# usb-100basefx.net
KiCad netlist of a schematic drawn in EAGLE
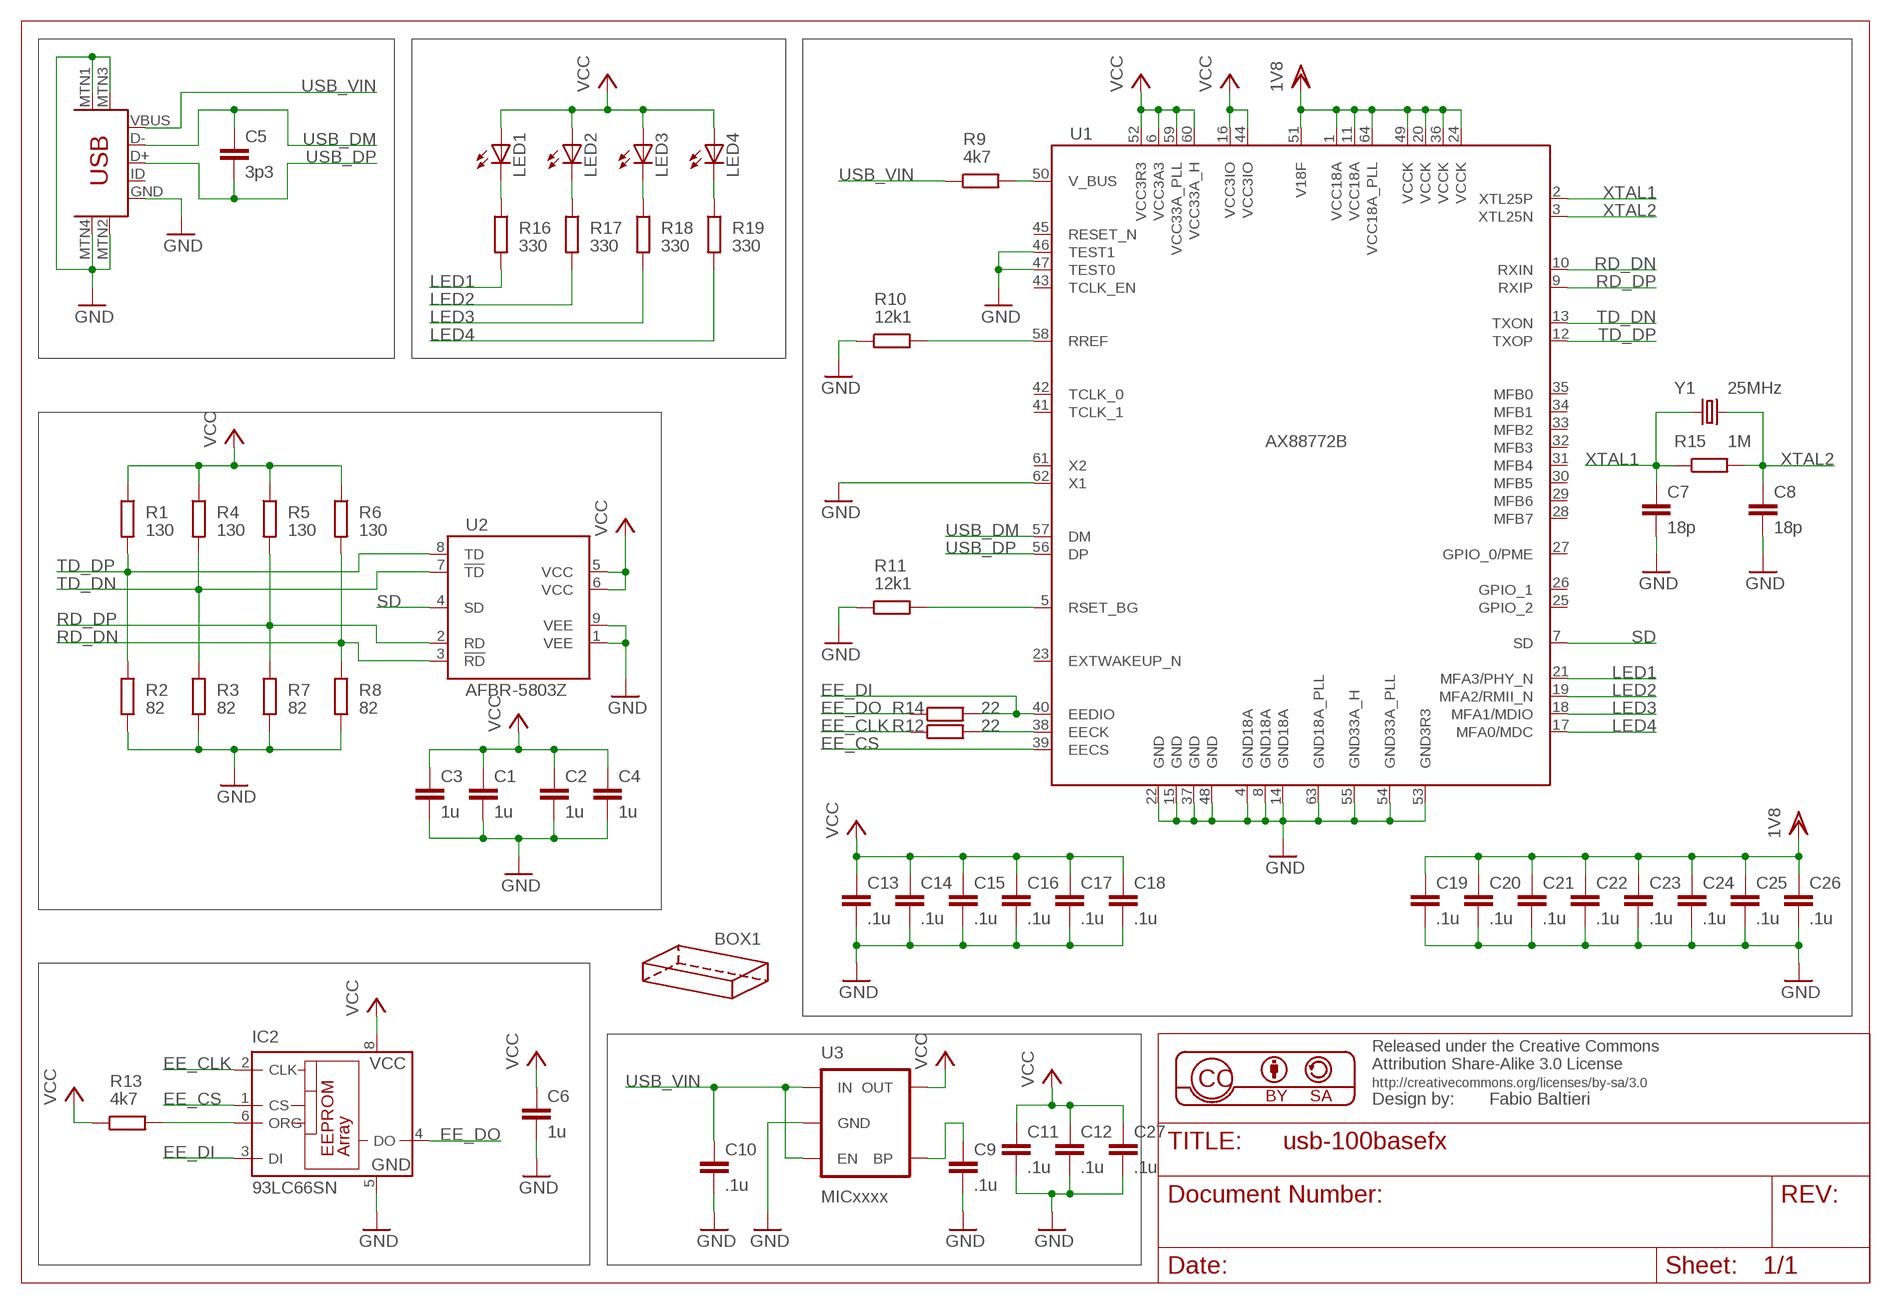
[diagram p0: schematic, sheet 1]

(export (version "E")
  (design (tool "Eeschema 10.0.6"))
  (components
    (comp (ref "BOX1")
      (value "HAMMOND-BOX-R")
      (footprint "eagle-import:1551R")
      (libsource (lib "eagle-import") (part "HAMMOND-BOX-R"))
    )
    (comp (ref "C1")
      (value "1u")
      (footprint "eagle-import:C0603")
      (libsource (lib "eagle-import") (part "C-EUC0603"))
    )
    (comp (ref "C2")
      (value "1u")
      (footprint "eagle-import:C0603")
      (libsource (lib "eagle-import") (part "C-EUC0603"))
    )
    (comp (ref "C3")
      (value "1u")
      (footprint "eagle-import:C0603")
      (libsource (lib "eagle-import") (part "C-EUC0603"))
    )
    (comp (ref "C4")
      (value "1u")
      (footprint "eagle-import:C0603")
      (libsource (lib "eagle-import") (part "C-EUC0603"))
    )
    (comp (ref "C5")
      (value "3p3")
      (footprint "eagle-import:C0603")
      (libsource (lib "eagle-import") (part "C-EUC0603"))
    )
    (comp (ref "C6")
      (value "1u")
      (footprint "eagle-import:C0603")
      (libsource (lib "eagle-import") (part "C-EUC0603"))
    )
    (comp (ref "C7")
      (value "18p")
      (footprint "eagle-import:C0603")
      (libsource (lib "eagle-import") (part "C-EUC0603"))
    )
    (comp (ref "C8")
      (value "18p")
      (footprint "eagle-import:C0603")
      (libsource (lib "eagle-import") (part "C-EUC0603"))
    )
    (comp (ref "C9")
      (value ".1u")
      (footprint "eagle-import:C0603")
      (libsource (lib "eagle-import") (part "C-EUC0603"))
    )
    (comp (ref "C10")
      (value ".1u")
      (footprint "eagle-import:C0603")
      (libsource (lib "eagle-import") (part "C-EUC0603"))
    )
    (comp (ref "C11")
      (value ".1u")
      (footprint "eagle-import:C0603")
      (libsource (lib "eagle-import") (part "C-EUC0603"))
    )
    (comp (ref "C12")
      (value ".1u")
      (footprint "eagle-import:C0603")
      (libsource (lib "eagle-import") (part "C-EUC0603"))
    )
    (comp (ref "C13")
      (value ".1u")
      (footprint "eagle-import:C0603")
      (libsource (lib "eagle-import") (part "C-EUC0603"))
    )
    (comp (ref "C14")
      (value ".1u")
      (footprint "eagle-import:C0603")
      (libsource (lib "eagle-import") (part "C-EUC0603"))
    )
    (comp (ref "C15")
      (value ".1u")
      (footprint "eagle-import:C0603")
      (libsource (lib "eagle-import") (part "C-EUC0603"))
    )
    (comp (ref "C16")
      (value ".1u")
      (footprint "eagle-import:C0603")
      (libsource (lib "eagle-import") (part "C-EUC0603"))
    )
    (comp (ref "C17")
      (value ".1u")
      (footprint "eagle-import:C0603")
      (libsource (lib "eagle-import") (part "C-EUC0603"))
    )
    (comp (ref "C18")
      (value ".1u")
      (footprint "eagle-import:C0603")
      (libsource (lib "eagle-import") (part "C-EUC0603"))
    )
    (comp (ref "C19")
      (value ".1u")
      (footprint "eagle-import:C0603")
      (libsource (lib "eagle-import") (part "C-EUC0603"))
    )
    (comp (ref "C20")
      (value ".1u")
      (footprint "eagle-import:C0603")
      (libsource (lib "eagle-import") (part "C-EUC0603"))
    )
    (comp (ref "C21")
      (value ".1u")
      (footprint "eagle-import:C0603")
      (libsource (lib "eagle-import") (part "C-EUC0603"))
    )
    (comp (ref "C22")
      (value ".1u")
      (footprint "eagle-import:C0603")
      (libsource (lib "eagle-import") (part "C-EUC0603"))
    )
    (comp (ref "C23")
      (value ".1u")
      (footprint "eagle-import:C0603")
      (libsource (lib "eagle-import") (part "C-EUC0603"))
    )
    (comp (ref "C24")
      (value ".1u")
      (footprint "eagle-import:C0603")
      (libsource (lib "eagle-import") (part "C-EUC0603"))
    )
    (comp (ref "C25")
      (value ".1u")
      (footprint "eagle-import:C0603")
      (libsource (lib "eagle-import") (part "C-EUC0603"))
    )
    (comp (ref "C26")
      (value ".1u")
      (footprint "eagle-import:C0603")
      (libsource (lib "eagle-import") (part "C-EUC0603"))
    )
    (comp (ref "C27")
      (value ".1u")
      (footprint "eagle-import:C0603")
      (libsource (lib "eagle-import") (part "C-EUC0603"))
    )
    (comp (ref "IC2")
      (value "93LC66SN")
      (footprint "eagle-import:SO-08")
      (fields (field (name "MF") "MICROCHIP") (field (name "MPN") "93LC66/SN"))
      (libsource (lib "eagle-import") (part "93SNLC66"))
    )
    (comp (ref "LED1")
      (value "LEDCHIPLED_0805")
      (footprint "eagle-import:CHIPLED_0805")
      (libsource (lib "eagle-import") (part "LEDCHIPLED_0805"))
    )
    (comp (ref "LED2")
      (value "LEDCHIPLED_0805")
      (footprint "eagle-import:CHIPLED_0805")
      (libsource (lib "eagle-import") (part "LEDCHIPLED_0805"))
    )
    (comp (ref "LED3")
      (value "LEDCHIPLED_0805")
      (footprint "eagle-import:CHIPLED_0805")
      (libsource (lib "eagle-import") (part "LEDCHIPLED_0805"))
    )
    (comp (ref "LED4")
      (value "LEDCHIPLED_0805")
      (footprint "eagle-import:CHIPLED_0805")
      (libsource (lib "eagle-import") (part "LEDCHIPLED_0805"))
    )
    (comp (ref "R1")
      (value "130")
      (footprint "eagle-import:R0603")
      (libsource (lib "eagle-import") (part "R-EU_R0603"))
    )
    (comp (ref "R2")
      (value "82")
      (footprint "eagle-import:R0603")
      (libsource (lib "eagle-import") (part "R-EU_R0603"))
    )
    (comp (ref "R3")
      (value "82")
      (footprint "eagle-import:R0603")
      (libsource (lib "eagle-import") (part "R-EU_R0603"))
    )
    (comp (ref "R4")
      (value "130")
      (footprint "eagle-import:R0603")
      (libsource (lib "eagle-import") (part "R-EU_R0603"))
    )
    (comp (ref "R5")
      (value "130")
      (footprint "eagle-import:R0603")
      (libsource (lib "eagle-import") (part "R-EU_R0603"))
    )
    (comp (ref "R6")
      (value "130")
      (footprint "eagle-import:R0603")
      (libsource (lib "eagle-import") (part "R-EU_R0603"))
    )
    (comp (ref "R7")
      (value "82")
      (footprint "eagle-import:R0603")
      (libsource (lib "eagle-import") (part "R-EU_R0603"))
    )
    (comp (ref "R8")
      (value "82")
      (footprint "eagle-import:R0603")
      (libsource (lib "eagle-import") (part "R-EU_R0603"))
    )
    (comp (ref "R9")
      (value "4k7")
      (footprint "eagle-import:R0603")
      (libsource (lib "eagle-import") (part "R-EU_R0603"))
    )
    (comp (ref "R10")
      (value "12k1")
      (footprint "eagle-import:R0603")
      (libsource (lib "eagle-import") (part "R-EU_R0603"))
    )
    (comp (ref "R11")
      (value "12k1")
      (footprint "eagle-import:R0603")
      (libsource (lib "eagle-import") (part "R-EU_R0603"))
    )
    (comp (ref "R12")
      (value "22")
      (footprint "eagle-import:R0603")
      (libsource (lib "eagle-import") (part "R-EU_R0603"))
    )
    (comp (ref "R13")
      (value "4k7")
      (footprint "eagle-import:R0603")
      (libsource (lib "eagle-import") (part "R-EU_R0603"))
    )
    (comp (ref "R14")
      (value "22")
      (footprint "eagle-import:R0603")
      (libsource (lib "eagle-import") (part "R-EU_R0603"))
    )
    (comp (ref "R15")
      (value "1M")
      (footprint "eagle-import:R0603")
      (libsource (lib "eagle-import") (part "R-EU_R0603"))
    )
    (comp (ref "R16")
      (value "330")
      (footprint "eagle-import:R0603")
      (libsource (lib "eagle-import") (part "R-EU_R0603"))
    )
    (comp (ref "R17")
      (value "330")
      (footprint "eagle-import:R0603")
      (libsource (lib "eagle-import") (part "R-EU_R0603"))
    )
    (comp (ref "R18")
      (value "330")
      (footprint "eagle-import:R0603")
      (libsource (lib "eagle-import") (part "R-EU_R0603"))
    )
    (comp (ref "R19")
      (value "330")
      (footprint "eagle-import:R0603")
      (libsource (lib "eagle-import") (part "R-EU_R0603"))
    )
    (comp (ref "U$1")
      (value "USB-MINIB-5PIN")
      (footprint "eagle-import:USB-MINIB")
      (libsource (lib "eagle-import") (part "USB-MINIB-5PIN"))
    )
    (comp (ref "U1")
      (value "AX88772B")
      (footprint "eagle-import:LQFP64")
      (libsource (lib "eagle-import") (part "AX88772B"))
    )
    (comp (ref "U2")
      (value "AFBR-5803Z")
      (footprint "eagle-import:AFBR-5803Z")
      (libsource (lib "eagle-import") (part "AFBR-5803Z"))
    )
    (comp (ref "U3")
      (value "MICxxxx")
      (footprint "eagle-import:SOT23-5")
      (libsource (lib "eagle-import") (part "V_REG_LDOSMD"))
    )
    (comp (ref "Y1")
      (value "25MHz")
      (footprint "eagle-import:CRYSTAL-SMD-5X3")
      (libsource (lib "eagle-import") (part "CRYSTAL5X3"))
    )
  )
  (nets
    (net (code "1") (name "/EE_CLK") (class "Default")
      (node (ref "IC2") (pin "2") (pinfunction "CLK_2") (pintype "input"))
      (node (ref "R12") (pin "1") (pinfunction "1_1") (pintype "passive"))
    )
    (net (code "2") (name "/EE_CS") (class "Default")
      (node (ref "IC2") (pin "1") (pinfunction "CS_1") (pintype "input"))
      (node (ref "U1") (pin "39") (pinfunction "EECS_39") (pintype "bidirectional"))
    )
    (net (code "3") (name "/EE_DI") (class "Default")
      (node (ref "IC2") (pin "3") (pinfunction "DI_3") (pintype "input"))
      (node (ref "R14") (pin "2") (pinfunction "2_2") (pintype "passive"))
      (node (ref "U1") (pin "40") (pinfunction "EEDIO_40") (pintype "bidirectional"))
    )
    (net (code "4") (name "/EE_DO") (class "Default")
      (node (ref "IC2") (pin "4") (pinfunction "DO_4") (pintype "tri_state"))
      (node (ref "R14") (pin "1") (pinfunction "1_1") (pintype "passive"))
    )
    (net (code "5") (name "/LED1") (class "Default")
      (node (ref "R16") (pin "2") (pinfunction "2_2") (pintype "passive"))
      (node (ref "U1") (pin "21") (pinfunction "MFA3/PHY_N_21") (pintype "bidirectional"))
    )
    (net (code "6") (name "/LED2") (class "Default")
      (node (ref "R17") (pin "2") (pinfunction "2_2") (pintype "passive"))
      (node (ref "U1") (pin "19") (pinfunction "MFA2/RMII_N_19") (pintype "bidirectional"))
    )
    (net (code "7") (name "/LED3") (class "Default")
      (node (ref "R18") (pin "2") (pinfunction "2_2") (pintype "passive"))
      (node (ref "U1") (pin "18") (pinfunction "MFA1/MDIO_18") (pintype "bidirectional"))
    )
    (net (code "8") (name "/LED4") (class "Default")
      (node (ref "R19") (pin "2") (pinfunction "2_2") (pintype "passive"))
      (node (ref "U1") (pin "17") (pinfunction "MFA0/MDC_17") (pintype "bidirectional"))
    )
    (net (code "9") (name "/RD_DN") (class "Default")
      (node (ref "R6") (pin "2") (pinfunction "2_2") (pintype "passive"))
      (node (ref "R8") (pin "1") (pinfunction "1_1") (pintype "passive"))
      (node (ref "U1") (pin "10") (pinfunction "RXIN_10") (pintype "bidirectional"))
      (node (ref "U2") (pin "3") (pinfunction "~{RD}_3") (pintype "bidirectional"))
    )
    (net (code "10") (name "/RD_DP") (class "Default")
      (node (ref "R5") (pin "2") (pinfunction "2_2") (pintype "passive"))
      (node (ref "R7") (pin "1") (pinfunction "1_1") (pintype "passive"))
      (node (ref "U1") (pin "9") (pinfunction "RXIP_9") (pintype "bidirectional"))
      (node (ref "U2") (pin "2") (pinfunction "RD_2") (pintype "bidirectional"))
    )
    (net (code "11") (name "/SD") (class "Default")
      (node (ref "U1") (pin "7") (pinfunction "SD_7") (pintype "bidirectional"))
      (node (ref "U2") (pin "4") (pinfunction "SD_4") (pintype "bidirectional"))
    )
    (net (code "12") (name "/TD_DN") (class "Default")
      (node (ref "R3") (pin "1") (pinfunction "1_1") (pintype "passive"))
      (node (ref "R4") (pin "2") (pinfunction "2_2") (pintype "passive"))
      (node (ref "U1") (pin "13") (pinfunction "TXON_13") (pintype "bidirectional"))
      (node (ref "U2") (pin "7") (pinfunction "~{TD}_7") (pintype "bidirectional"))
    )
    (net (code "13") (name "/TD_DP") (class "Default")
      (node (ref "R1") (pin "2") (pinfunction "2_2") (pintype "passive"))
      (node (ref "R2") (pin "1") (pinfunction "1_1") (pintype "passive"))
      (node (ref "U1") (pin "12") (pinfunction "TXOP_12") (pintype "bidirectional"))
      (node (ref "U2") (pin "8") (pinfunction "TD_8") (pintype "bidirectional"))
    )
    (net (code "14") (name "/USB_DM") (class "Default")
      (node (ref "C5") (pin "1") (pinfunction "1_1") (pintype "passive"))
      (node (ref "U$1") (pin "D-") (pinfunction "D-_D-") (pintype "bidirectional"))
      (node (ref "U1") (pin "57") (pinfunction "DM_57") (pintype "bidirectional"))
    )
    (net (code "15") (name "/USB_DP") (class "Default")
      (node (ref "C5") (pin "2") (pinfunction "2_2") (pintype "passive"))
      (node (ref "U$1") (pin "D+") (pinfunction "D+_D+") (pintype "bidirectional"))
      (node (ref "U1") (pin "56") (pinfunction "DP_56") (pintype "bidirectional"))
    )
    (net (code "16") (name "/USB_VIN") (class "Default")
      (node (ref "C10") (pin "1") (pinfunction "1_1") (pintype "passive"))
      (node (ref "R9") (pin "1") (pinfunction "1_1") (pintype "passive"))
      (node (ref "U$1") (pin "VBUS") (pinfunction "VBUS_VBUS") (pintype "bidirectional"))
      (node (ref "U3") (pin "1") (pinfunction "IN_1") (pintype "input"))
      (node (ref "U3") (pin "3") (pinfunction "EN_3") (pintype "input"))
    )
    (net (code "17") (name "/XTAL1") (class "Default")
      (node (ref "C7") (pin "1") (pinfunction "1_1") (pintype "passive"))
      (node (ref "R15") (pin "1") (pinfunction "1_1") (pintype "passive"))
      (node (ref "U1") (pin "2") (pinfunction "XTL25P_2") (pintype "bidirectional"))
      (node (ref "Y1") (pin "1") (pinfunction "1_1") (pintype "passive"))
    )
    (net (code "18") (name "/XTAL2") (class "Default")
      (node (ref "C8") (pin "1") (pinfunction "1_1") (pintype "passive"))
      (node (ref "R15") (pin "2") (pinfunction "2_2") (pintype "passive"))
      (node (ref "U1") (pin "3") (pinfunction "XTL25N_3") (pintype "bidirectional"))
      (node (ref "Y1") (pin "3") (pinfunction "2_3") (pintype "passive"))
    )
    (net (code "19") (name "1V8") (class "Default")
      (node (ref "C19") (pin "1") (pinfunction "1_1") (pintype "passive"))
      (node (ref "C20") (pin "1") (pinfunction "1_1") (pintype "passive"))
      (node (ref "C21") (pin "1") (pinfunction "1_1") (pintype "passive"))
      (node (ref "C22") (pin "1") (pinfunction "1_1") (pintype "passive"))
      (node (ref "C23") (pin "1") (pinfunction "1_1") (pintype "passive"))
      (node (ref "C24") (pin "1") (pinfunction "1_1") (pintype "passive"))
      (node (ref "C25") (pin "1") (pinfunction "1_1") (pintype "passive"))
      (node (ref "C26") (pin "1") (pinfunction "1_1") (pintype "passive"))
      (node (ref "U1") (pin "1") (pinfunction "VCC18A_1") (pintype "bidirectional"))
      (node (ref "U1") (pin "11") (pinfunction "VCC18A_11") (pintype "bidirectional"))
      (node (ref "U1") (pin "20") (pinfunction "VCCK_20") (pintype "bidirectional"))
      (node (ref "U1") (pin "24") (pinfunction "VCCK_24") (pintype "bidirectional"))
      (node (ref "U1") (pin "36") (pinfunction "VCCK_36") (pintype "bidirectional"))
      (node (ref "U1") (pin "49") (pinfunction "VCCK_49") (pintype "bidirectional"))
      (node (ref "U1") (pin "51") (pinfunction "V18F_51") (pintype "bidirectional"))
      (node (ref "U1") (pin "64") (pinfunction "VCC18A_PLL_64") (pintype "bidirectional"))
    )
    (net (code "20") (name "GND") (class "Default")
      (node (ref "C1") (pin "2") (pinfunction "2_2") (pintype "passive"))
      (node (ref "C10") (pin "2") (pinfunction "2_2") (pintype "passive"))
      (node (ref "C11") (pin "2") (pinfunction "2_2") (pintype "passive"))
      (node (ref "C12") (pin "2") (pinfunction "2_2") (pintype "passive"))
      (node (ref "C13") (pin "2") (pinfunction "2_2") (pintype "passive"))
      (node (ref "C14") (pin "2") (pinfunction "2_2") (pintype "passive"))
      (node (ref "C15") (pin "2") (pinfunction "2_2") (pintype "passive"))
      (node (ref "C16") (pin "2") (pinfunction "2_2") (pintype "passive"))
      (node (ref "C17") (pin "2") (pinfunction "2_2") (pintype "passive"))
      (node (ref "C18") (pin "2") (pinfunction "2_2") (pintype "passive"))
      (node (ref "C19") (pin "2") (pinfunction "2_2") (pintype "passive"))
      (node (ref "C2") (pin "2") (pinfunction "2_2") (pintype "passive"))
      (node (ref "C20") (pin "2") (pinfunction "2_2") (pintype "passive"))
      (node (ref "C21") (pin "2") (pinfunction "2_2") (pintype "passive"))
      (node (ref "C22") (pin "2") (pinfunction "2_2") (pintype "passive"))
      (node (ref "C23") (pin "2") (pinfunction "2_2") (pintype "passive"))
      (node (ref "C24") (pin "2") (pinfunction "2_2") (pintype "passive"))
      (node (ref "C25") (pin "2") (pinfunction "2_2") (pintype "passive"))
      (node (ref "C26") (pin "2") (pinfunction "2_2") (pintype "passive"))
      (node (ref "C27") (pin "2") (pinfunction "2_2") (pintype "passive"))
      (node (ref "C3") (pin "2") (pinfunction "2_2") (pintype "passive"))
      (node (ref "C4") (pin "2") (pinfunction "2_2") (pintype "passive"))
      (node (ref "C6") (pin "2") (pinfunction "2_2") (pintype "passive"))
      (node (ref "C7") (pin "2") (pinfunction "2_2") (pintype "passive"))
      (node (ref "C8") (pin "2") (pinfunction "2_2") (pintype "passive"))
      (node (ref "C9") (pin "2") (pinfunction "2_2") (pintype "passive"))
      (node (ref "IC2") (pin "5") (pinfunction "GND_5") (pintype "power_in"))
      (node (ref "R10") (pin "1") (pinfunction "1_1") (pintype "passive"))
      (node (ref "R11") (pin "1") (pinfunction "1_1") (pintype "passive"))
      (node (ref "R2") (pin "2") (pinfunction "2_2") (pintype "passive"))
      (node (ref "R3") (pin "2") (pinfunction "2_2") (pintype "passive"))
      (node (ref "R7") (pin "2") (pinfunction "2_2") (pintype "passive"))
      (node (ref "R8") (pin "2") (pinfunction "2_2") (pintype "passive"))
      (node (ref "U$1") (pin "GND") (pinfunction "GND_GND") (pintype "bidirectional"))
      (node (ref "U$1") (pin "MTN1") (pinfunction "MTN2_MTN1") (pintype "bidirectional"))
      (node (ref "U$1") (pin "MTN2") (pinfunction "MTN3_MTN2") (pintype "bidirectional"))
      (node (ref "U$1") (pin "MTN3") (pinfunction "MTN1_MTN3") (pintype "bidirectional"))
      (node (ref "U$1") (pin "MTN4") (pinfunction "MTN4_MTN4") (pintype "bidirectional"))
      (node (ref "U1") (pin "14") (pinfunction "GND18A_14") (pintype "bidirectional"))
      (node (ref "U1") (pin "15") (pinfunction "GND_15") (pintype "bidirectional"))
      (node (ref "U1") (pin "22") (pinfunction "GND_22") (pintype "bidirectional"))
      (node (ref "U1") (pin "37") (pinfunction "GND_37") (pintype "bidirectional"))
      (node (ref "U1") (pin "4") (pinfunction "GND18A_4") (pintype "bidirectional"))
      (node (ref "U1") (pin "46") (pinfunction "TEST1_46") (pintype "bidirectional"))
      (node (ref "U1") (pin "47") (pinfunction "TEST0_47") (pintype "bidirectional"))
      (node (ref "U1") (pin "48") (pinfunction "GND_48") (pintype "bidirectional"))
      (node (ref "U1") (pin "53") (pinfunction "GND3R3_53") (pintype "bidirectional"))
      (node (ref "U1") (pin "54") (pinfunction "GND33A_PLL_54") (pintype "bidirectional"))
      (node (ref "U1") (pin "55") (pinfunction "GND33A_H_55") (pintype "bidirectional"))
      (node (ref "U1") (pin "62") (pinfunction "X1_62") (pintype "bidirectional"))
      (node (ref "U1") (pin "63") (pinfunction "GND18A_PLL_63") (pintype "bidirectional"))
      (node (ref "U1") (pin "8") (pinfunction "GND18A_8") (pintype "bidirectional"))
      (node (ref "U2") (pin "1") (pinfunction "VEE_1") (pintype "bidirectional"))
      (node (ref "U2") (pin "9") (pinfunction "VEE_9") (pintype "bidirectional"))
      (node (ref "U3") (pin "2") (pinfunction "GND_2") (pintype "input"))
    )
    (net (code "21") (name "Net-(IC2-ORG)") (class "Default")
      (node (ref "IC2") (pin "6") (pinfunction "ORG_6") (pintype "input"))
      (node (ref "R13") (pin "2") (pinfunction "2_2") (pintype "passive"))
    )
    (net (code "22") (name "Net-(LED1-PadC)") (class "Default")
      (node (ref "LED1") (pin "C") (pinfunction "C_C") (pintype "passive"))
      (node (ref "R16") (pin "1") (pinfunction "1_1") (pintype "passive"))
    )
    (net (code "23") (name "Net-(LED2-PadC)") (class "Default")
      (node (ref "LED2") (pin "C") (pinfunction "C_C") (pintype "passive"))
      (node (ref "R17") (pin "1") (pinfunction "1_1") (pintype "passive"))
    )
    (net (code "24") (name "Net-(LED3-PadC)") (class "Default")
      (node (ref "LED3") (pin "C") (pinfunction "C_C") (pintype "passive"))
      (node (ref "R18") (pin "1") (pinfunction "1_1") (pintype "passive"))
    )
    (net (code "25") (name "Net-(LED4-PadC)") (class "Default")
      (node (ref "LED4") (pin "C") (pinfunction "C_C") (pintype "passive"))
      (node (ref "R19") (pin "1") (pinfunction "1_1") (pintype "passive"))
    )
    (net (code "26") (name "Net-(U1-EECK)") (class "Default")
      (node (ref "R12") (pin "2") (pinfunction "2_2") (pintype "passive"))
      (node (ref "U1") (pin "38") (pinfunction "EECK_38") (pintype "bidirectional"))
    )
    (net (code "27") (name "Net-(U1-RREF)") (class "Default")
      (node (ref "R10") (pin "2") (pinfunction "2_2") (pintype "passive"))
      (node (ref "U1") (pin "58") (pinfunction "RREF_58") (pintype "bidirectional"))
    )
    (net (code "28") (name "Net-(U1-RSET_BG)") (class "Default")
      (node (ref "R11") (pin "2") (pinfunction "2_2") (pintype "passive"))
      (node (ref "U1") (pin "5") (pinfunction "RSET_BG_5") (pintype "bidirectional"))
    )
    (net (code "29") (name "Net-(U1-V_BUS)") (class "Default")
      (node (ref "R9") (pin "2") (pinfunction "2_2") (pintype "passive"))
      (node (ref "U1") (pin "50") (pinfunction "V_BUS_50") (pintype "bidirectional"))
    )
    (net (code "30") (name "Net-(U3-BP)") (class "Default")
      (node (ref "C9") (pin "1") (pinfunction "1_1") (pintype "passive"))
      (node (ref "U3") (pin "4") (pinfunction "BP_4") (pintype "input"))
    )
    (net (code "31") (name "VCC") (class "Default")
      (node (ref "C1") (pin "1") (pinfunction "1_1") (pintype "passive"))
      (node (ref "C11") (pin "1") (pinfunction "1_1") (pintype "passive"))
      (node (ref "C12") (pin "1") (pinfunction "1_1") (pintype "passive"))
      (node (ref "C13") (pin "1") (pinfunction "1_1") (pintype "passive"))
      (node (ref "C14") (pin "1") (pinfunction "1_1") (pintype "passive"))
      (node (ref "C15") (pin "1") (pinfunction "1_1") (pintype "passive"))
      (node (ref "C16") (pin "1") (pinfunction "1_1") (pintype "passive"))
      (node (ref "C17") (pin "1") (pinfunction "1_1") (pintype "passive"))
      (node (ref "C18") (pin "1") (pinfunction "1_1") (pintype "passive"))
      (node (ref "C2") (pin "1") (pinfunction "1_1") (pintype "passive"))
      (node (ref "C27") (pin "1") (pinfunction "1_1") (pintype "passive"))
      (node (ref "C3") (pin "1") (pinfunction "1_1") (pintype "passive"))
      (node (ref "C4") (pin "1") (pinfunction "1_1") (pintype "passive"))
      (node (ref "C6") (pin "1") (pinfunction "1_1") (pintype "passive"))
      (node (ref "IC2") (pin "8") (pinfunction "VCC_8") (pintype "power_in"))
      (node (ref "LED1") (pin "A") (pinfunction "A_A") (pintype "passive"))
      (node (ref "LED2") (pin "A") (pinfunction "A_A") (pintype "passive"))
      (node (ref "LED3") (pin "A") (pinfunction "A_A") (pintype "passive"))
      (node (ref "LED4") (pin "A") (pinfunction "A_A") (pintype "passive"))
      (node (ref "R1") (pin "1") (pinfunction "1_1") (pintype "passive"))
      (node (ref "R13") (pin "1") (pinfunction "1_1") (pintype "passive"))
      (node (ref "R4") (pin "1") (pinfunction "1_1") (pintype "passive"))
      (node (ref "R5") (pin "1") (pinfunction "1_1") (pintype "passive"))
      (node (ref "R6") (pin "1") (pinfunction "1_1") (pintype "passive"))
      (node (ref "U1") (pin "16") (pinfunction "VCC3IO_16") (pintype "bidirectional"))
      (node (ref "U1") (pin "44") (pinfunction "VCC3IO_44") (pintype "bidirectional"))
      (node (ref "U1") (pin "52") (pinfunction "VCC3R3_52") (pintype "bidirectional"))
      (node (ref "U1") (pin "59") (pinfunction "VCC33A_PLL_59") (pintype "bidirectional"))
      (node (ref "U1") (pin "6") (pinfunction "VCC3A3_6") (pintype "bidirectional"))
      (node (ref "U1") (pin "60") (pinfunction "VCC33A_H_60") (pintype "bidirectional"))
      (node (ref "U2") (pin "5") (pinfunction "VCC_5") (pintype "bidirectional"))
      (node (ref "U2") (pin "6") (pinfunction "VCC_6") (pintype "bidirectional"))
      (node (ref "U3") (pin "5") (pinfunction "OUT_5") (pintype "passive"))
    )
    (net (code "32") (name "unconnected-(IC2-NU-Pad7)") (class "Default")
      (node (ref "IC2") (pin "7") (pinfunction "NU_7") (pintype "passive"))
    )
    (net (code "33") (name "unconnected-(U$1-PadID)") (class "Default")
      (node (ref "U$1") (pin "ID") (pinfunction "ID_ID") (pintype "bidirectional"))
    )
    (net (code "34") (name "unconnected-(U1-EXTWAKEUP_N-Pad23)") (class "Default")
      (node (ref "U1") (pin "23") (pinfunction "EXTWAKEUP_N_23") (pintype "bidirectional"))
    )
    (net (code "35") (name "unconnected-(U1-GPIO_0{slash}PME-Pad27)") (class "Default")
      (node (ref "U1") (pin "27") (pinfunction "GPIO_0/PME_27") (pintype "bidirectional"))
    )
    (net (code "36") (name "unconnected-(U1-GPIO_1-Pad26)") (class "Default")
      (node (ref "U1") (pin "26") (pinfunction "GPIO_1_26") (pintype "bidirectional"))
    )
    (net (code "37") (name "unconnected-(U1-GPIO_2-Pad25)") (class "Default")
      (node (ref "U1") (pin "25") (pinfunction "GPIO_2_25") (pintype "bidirectional"))
    )
    (net (code "38") (name "unconnected-(U1-MFB0-Pad35)") (class "Default")
      (node (ref "U1") (pin "35") (pinfunction "MFB0_35") (pintype "bidirectional"))
    )
    (net (code "39") (name "unconnected-(U1-MFB1-Pad34)") (class "Default")
      (node (ref "U1") (pin "34") (pinfunction "MFB1_34") (pintype "bidirectional"))
    )
    (net (code "40") (name "unconnected-(U1-MFB2-Pad33)") (class "Default")
      (node (ref "U1") (pin "33") (pinfunction "MFB2_33") (pintype "bidirectional"))
    )
    (net (code "41") (name "unconnected-(U1-MFB3-Pad32)") (class "Default")
      (node (ref "U1") (pin "32") (pinfunction "MFB3_32") (pintype "bidirectional"))
    )
    (net (code "42") (name "unconnected-(U1-MFB4-Pad31)") (class "Default")
      (node (ref "U1") (pin "31") (pinfunction "MFB4_31") (pintype "bidirectional"))
    )
    (net (code "43") (name "unconnected-(U1-MFB5-Pad30)") (class "Default")
      (node (ref "U1") (pin "30") (pinfunction "MFB5_30") (pintype "bidirectional"))
    )
    (net (code "44") (name "unconnected-(U1-MFB6-Pad29)") (class "Default")
      (node (ref "U1") (pin "29") (pinfunction "MFB6_29") (pintype "bidirectional"))
    )
    (net (code "45") (name "unconnected-(U1-MFB7-Pad28)") (class "Default")
      (node (ref "U1") (pin "28") (pinfunction "MFB7_28") (pintype "bidirectional"))
    )
    (net (code "46") (name "unconnected-(U1-RESET_N-Pad45)") (class "Default")
      (node (ref "U1") (pin "45") (pinfunction "RESET_N_45") (pintype "bidirectional"))
    )
    (net (code "47") (name "unconnected-(U1-TCLK_0-Pad42)") (class "Default")
      (node (ref "U1") (pin "42") (pinfunction "TCLK_0_42") (pintype "bidirectional"))
    )
    (net (code "48") (name "unconnected-(U1-TCLK_1-Pad41)") (class "Default")
      (node (ref "U1") (pin "41") (pinfunction "TCLK_1_41") (pintype "bidirectional"))
    )
    (net (code "49") (name "unconnected-(U1-TCLK_EN-Pad43)") (class "Default")
      (node (ref "U1") (pin "43") (pinfunction "TCLK_EN_43") (pintype "bidirectional"))
    )
    (net (code "50") (name "unconnected-(U1-X2-Pad61)") (class "Default")
      (node (ref "U1") (pin "61") (pinfunction "X2_61") (pintype "bidirectional"))
    )
  )
)
